# MCU.net
KiCad netlist of a schematic drawn in Altium Designer
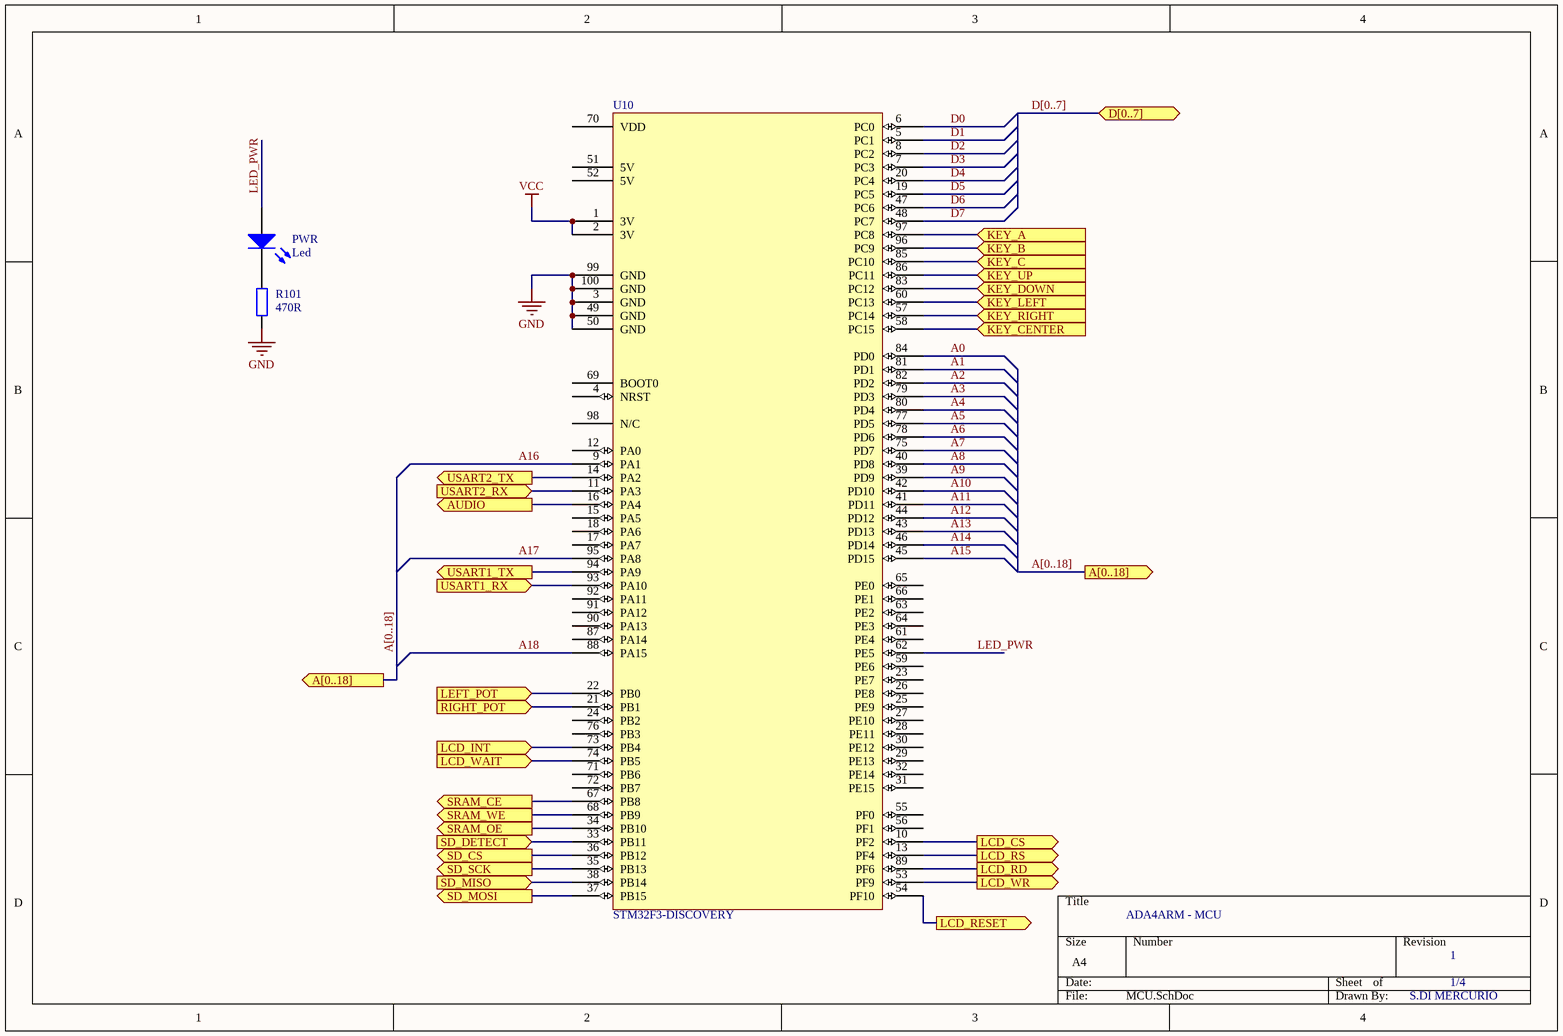
[diagram p0: MCU.SchDoc]

(export (version "E")
  (design (tool "Eeschema 10.0.6"))
  (components
    (comp (ref "PWR") (value "Led") (footprint "OSRAM LO Q971") (libsource (lib "INSA") (part "Led")))
    (comp (ref "R101")
      (value "470R")
      (footprint "RESC3216N")
      (description "Resistor")
      (fields (field (name "Comment") "Res_EU") (field (name "PUBLISHER") "Altium Limited"))
      (libsource (lib "Miscellaneous INSA") (part "Res_EU"))
    )
    (comp (ref "U10")
      (value "STM32F3-DISCOVERY")
      (footprint "STM32F3-DISCOVERY")
      (description "STM32F3-Discovery")
      (libsource (lib "INSA") (part "STM32F3-DISCOVERY"))
    )
  )
  (nets
    (net (code "1") (name "/A0") (class "Default")
      (node (ref "U10") (pin "84") (pinfunction "PD0_84") (pintype "bidirectional"))
    )
    (net (code "2") (name "/A1") (class "Default")
      (node (ref "U10") (pin "81") (pinfunction "PD1_81") (pintype "bidirectional"))
    )
    (net (code "3") (name "/A2") (class "Default")
      (node (ref "U10") (pin "82") (pinfunction "PD2_82") (pintype "bidirectional"))
    )
    (net (code "4") (name "/A3") (class "Default")
      (node (ref "U10") (pin "79") (pinfunction "PD3_79") (pintype "bidirectional"))
    )
    (net (code "5") (name "/A4") (class "Default")
      (node (ref "U10") (pin "80") (pinfunction "PD4_80") (pintype "bidirectional"))
    )
    (net (code "6") (name "/A5") (class "Default")
      (node (ref "U10") (pin "77") (pinfunction "PD5_77") (pintype "bidirectional"))
    )
    (net (code "7") (name "/A6") (class "Default")
      (node (ref "U10") (pin "78") (pinfunction "PD6_78") (pintype "bidirectional"))
    )
    (net (code "8") (name "/A7") (class "Default")
      (node (ref "U10") (pin "75") (pinfunction "PD7_75") (pintype "bidirectional"))
    )
    (net (code "9") (name "/A8") (class "Default")
      (node (ref "U10") (pin "40") (pinfunction "PD8_40") (pintype "bidirectional"))
    )
    (net (code "10") (name "/A9") (class "Default")
      (node (ref "U10") (pin "39") (pinfunction "PD9_39") (pintype "bidirectional"))
    )
    (net (code "11") (name "/A10") (class "Default")
      (node (ref "U10") (pin "42") (pinfunction "PD10_42") (pintype "bidirectional"))
    )
    (net (code "12") (name "/A11") (class "Default")
      (node (ref "U10") (pin "41") (pinfunction "PD11_41") (pintype "bidirectional"))
    )
    (net (code "13") (name "/A12") (class "Default")
      (node (ref "U10") (pin "44") (pinfunction "PD12_44") (pintype "bidirectional"))
    )
    (net (code "14") (name "/A13") (class "Default")
      (node (ref "U10") (pin "43") (pinfunction "PD13_43") (pintype "bidirectional"))
    )
    (net (code "15") (name "/A14") (class "Default")
      (node (ref "U10") (pin "46") (pinfunction "PD14_46") (pintype "bidirectional"))
    )
    (net (code "16") (name "/A15") (class "Default")
      (node (ref "U10") (pin "45") (pinfunction "PD15_45") (pintype "bidirectional"))
    )
    (net (code "17") (name "/A16") (class "Default")
      (node (ref "U10") (pin "9") (pinfunction "PA1_9") (pintype "bidirectional"))
    )
    (net (code "18") (name "/A17") (class "Default")
      (node (ref "U10") (pin "95") (pinfunction "PA8_95") (pintype "bidirectional"))
    )
    (net (code "19") (name "/A18") (class "Default")
      (node (ref "U10") (pin "88") (pinfunction "PA15_88") (pintype "bidirectional"))
    )
    (net (code "20") (name "/AUDIO") (class "Default")
      (node (ref "U10") (pin "16") (pinfunction "PA4_16") (pintype "bidirectional"))
    )
    (net (code "22") (name "/D0") (class "Default")
      (node (ref "U10") (pin "6") (pinfunction "PC0_6") (pintype "bidirectional"))
    )
    (net (code "23") (name "/D1") (class "Default")
      (node (ref "U10") (pin "5") (pinfunction "PC1_5") (pintype "bidirectional"))
    )
    (net (code "24") (name "/D2") (class "Default")
      (node (ref "U10") (pin "8") (pinfunction "PC2_8") (pintype "bidirectional"))
    )
    (net (code "25") (name "/D3") (class "Default")
      (node (ref "U10") (pin "7") (pinfunction "PC3_7") (pintype "bidirectional"))
    )
    (net (code "26") (name "/D4") (class "Default")
      (node (ref "U10") (pin "20") (pinfunction "PC4_20") (pintype "bidirectional"))
    )
    (net (code "27") (name "/D5") (class "Default")
      (node (ref "U10") (pin "19") (pinfunction "PC5_19") (pintype "bidirectional"))
    )
    (net (code "28") (name "/D6") (class "Default")
      (node (ref "U10") (pin "47") (pinfunction "PC6_47") (pintype "bidirectional"))
    )
    (net (code "29") (name "/D7") (class "Default")
      (node (ref "U10") (pin "48") (pinfunction "PC7_48") (pintype "bidirectional"))
    )
    (net (code "31") (name "/KEY_A") (class "Default")
      (node (ref "U10") (pin "97") (pinfunction "PC8_97") (pintype "bidirectional"))
    )
    (net (code "32") (name "/KEY_B") (class "Default")
      (node (ref "U10") (pin "96") (pinfunction "PC9_96") (pintype "bidirectional"))
    )
    (net (code "33") (name "/KEY_C") (class "Default")
      (node (ref "U10") (pin "85") (pinfunction "PC10_85") (pintype "bidirectional"))
    )
    (net (code "34") (name "/KEY_CENTER") (class "Default")
      (node (ref "U10") (pin "58") (pinfunction "PC15_58") (pintype "bidirectional"))
    )
    (net (code "35") (name "/KEY_DOWN") (class "Default")
      (node (ref "U10") (pin "83") (pinfunction "PC12_83") (pintype "bidirectional"))
    )
    (net (code "36") (name "/KEY_LEFT") (class "Default")
      (node (ref "U10") (pin "60") (pinfunction "PC13_60") (pintype "bidirectional"))
    )
    (net (code "37") (name "/KEY_RIGHT") (class "Default")
      (node (ref "U10") (pin "57") (pinfunction "PC14_57") (pintype "bidirectional"))
    )
    (net (code "38") (name "/KEY_UP") (class "Default")
      (node (ref "U10") (pin "86") (pinfunction "PC11_86") (pintype "bidirectional"))
    )
    (net (code "39") (name "/LCD_CS") (class "Default")
      (node (ref "U10") (pin "10") (pinfunction "PF2_10") (pintype "bidirectional"))
    )
    (net (code "40") (name "/LCD_INT") (class "Default")
      (node (ref "U10") (pin "73") (pinfunction "PB4_73") (pintype "bidirectional"))
    )
    (net (code "41") (name "/LCD_RD") (class "Default")
      (node (ref "U10") (pin "89") (pinfunction "PF6_89") (pintype "bidirectional"))
    )
    (net (code "42") (name "/LCD_RESET") (class "Default")
      (node (ref "U10") (pin "54") (pinfunction "PF10_54") (pintype "bidirectional"))
    )
    (net (code "43") (name "/LCD_RS") (class "Default")
      (node (ref "U10") (pin "13") (pinfunction "PF4_13") (pintype "bidirectional"))
    )
    (net (code "44") (name "/LCD_WAIT") (class "Default")
      (node (ref "U10") (pin "74") (pinfunction "PB5_74") (pintype "bidirectional"))
    )
    (net (code "45") (name "/LCD_WR") (class "Default")
      (node (ref "U10") (pin "53") (pinfunction "PF9_53") (pintype "bidirectional"))
    )
    (net (code "46") (name "/LED_PWR") (class "Default")
      (node (ref "PWR") (pin "A") (pinfunction "A_A") (pintype "passive"))
      (node (ref "U10") (pin "62") (pinfunction "PE5_62") (pintype "bidirectional"))
    )
    (net (code "47") (name "/LEFT_POT") (class "Default")
      (node (ref "U10") (pin "22") (pinfunction "PB0_22") (pintype "bidirectional"))
    )
    (net (code "48") (name "/RIGHT_POT") (class "Default")
      (node (ref "U10") (pin "21") (pinfunction "PB1_21") (pintype "bidirectional"))
    )
    (net (code "49") (name "/SD_CS") (class "Default")
      (node (ref "U10") (pin "36") (pinfunction "PB12_36") (pintype "bidirectional"))
    )
    (net (code "50") (name "/SD_DETECT") (class "Default")
      (node (ref "U10") (pin "33") (pinfunction "PB11_33") (pintype "bidirectional"))
    )
    (net (code "51") (name "/SD_MISO") (class "Default")
      (node (ref "U10") (pin "38") (pinfunction "PB14_38") (pintype "bidirectional"))
    )
    (net (code "52") (name "/SD_MOSI") (class "Default")
      (node (ref "U10") (pin "37") (pinfunction "PB15_37") (pintype "bidirectional"))
    )
    (net (code "53") (name "/SD_SCK") (class "Default")
      (node (ref "U10") (pin "35") (pinfunction "PB13_35") (pintype "bidirectional"))
    )
    (net (code "54") (name "/SRAM_CE") (class "Default")
      (node (ref "U10") (pin "67") (pinfunction "PB8_67") (pintype "bidirectional"))
    )
    (net (code "55") (name "/SRAM_OE") (class "Default")
      (node (ref "U10") (pin "34") (pinfunction "PB10_34") (pintype "bidirectional"))
    )
    (net (code "56") (name "/SRAM_WE") (class "Default")
      (node (ref "U10") (pin "68") (pinfunction "PB9_68") (pintype "bidirectional"))
    )
    (net (code "57") (name "/USART1_RX") (class "Default")
      (node (ref "U10") (pin "93") (pinfunction "PA10_93") (pintype "bidirectional"))
    )
    (net (code "58") (name "/USART1_TX") (class "Default")
      (node (ref "U10") (pin "94") (pinfunction "PA9_94") (pintype "bidirectional"))
    )
    (net (code "59") (name "/USART2_RX") (class "Default")
      (node (ref "U10") (pin "11") (pinfunction "PA3_11") (pintype "bidirectional"))
    )
    (net (code "60") (name "/USART2_TX") (class "Default")
      (node (ref "U10") (pin "14") (pinfunction "PA2_14") (pintype "bidirectional"))
    )
    (net (code "61") (name "GND") (class "Default")
      (node (ref "R101") (pin "1") (pinfunction "1_1") (pintype "passive"))
      (node (ref "U10") (pin "100") (pinfunction "GND_100") (pintype "power_in"))
      (node (ref "U10") (pin "3") (pinfunction "GND_3") (pintype "power_in"))
      (node (ref "U10") (pin "49") (pinfunction "GND_49") (pintype "power_in"))
      (node (ref "U10") (pin "50") (pinfunction "GND_50") (pintype "power_in"))
      (node (ref "U10") (pin "99") (pinfunction "GND_99") (pintype "power_in"))
    )
    (net (code "62") (name "Net-(PWR-PadK)") (class "Default")
      (node (ref "PWR") (pin "K") (pinfunction "K_K") (pintype "passive"))
      (node (ref "R101") (pin "2") (pinfunction "2_2") (pintype "passive"))
    )
    (net (code "63") (name "VCC") (class "Default")
      (node (ref "U10") (pin "1") (pinfunction "3V_1") (pintype "power_in"))
      (node (ref "U10") (pin "2") (pinfunction "3V_2") (pintype "power_in"))
    )
    (net (code "64") (name "unconnected-(U10-5V-Pad51)") (class "Default")
      (node (ref "U10") (pin "51") (pinfunction "5V_51") (pintype "power_in"))
    )
    (net (code "65") (name "unconnected-(U10-5V-Pad52)") (class "Default")
      (node (ref "U10") (pin "52") (pinfunction "5V_52") (pintype "power_in"))
    )
    (net (code "66") (name "unconnected-(U10-BOOT0-Pad69)") (class "Default")
      (node (ref "U10") (pin "69") (pinfunction "BOOT0_69") (pintype "passive"))
    )
    (net (code "67") (name "unconnected-(U10-NRST-Pad4)") (class "Default")
      (node (ref "U10") (pin "4") (pinfunction "NRST_4") (pintype "bidirectional"))
    )
    (net (code "68") (name "unconnected-(U10-N{slash}C-Pad98)") (class "Default")
      (node (ref "U10") (pin "98") (pinfunction "N/C_98") (pintype "passive"))
    )
    (net (code "69") (name "unconnected-(U10-PA0-Pad12)") (class "Default")
      (node (ref "U10") (pin "12") (pinfunction "PA0_12") (pintype "bidirectional"))
    )
    (net (code "70") (name "unconnected-(U10-PA5-Pad15)") (class "Default")
      (node (ref "U10") (pin "15") (pinfunction "PA5_15") (pintype "bidirectional"))
    )
    (net (code "71") (name "unconnected-(U10-PA6-Pad18)") (class "Default")
      (node (ref "U10") (pin "18") (pinfunction "PA6_18") (pintype "bidirectional"))
    )
    (net (code "72") (name "unconnected-(U10-PA7-Pad17)") (class "Default")
      (node (ref "U10") (pin "17") (pinfunction "PA7_17") (pintype "bidirectional"))
    )
    (net (code "73") (name "unconnected-(U10-PA11-Pad92)") (class "Default")
      (node (ref "U10") (pin "92") (pinfunction "PA11_92") (pintype "bidirectional"))
    )
    (net (code "74") (name "unconnected-(U10-PA12-Pad91)") (class "Default")
      (node (ref "U10") (pin "91") (pinfunction "PA12_91") (pintype "bidirectional"))
    )
    (net (code "75") (name "unconnected-(U10-PA13-Pad90)") (class "Default")
      (node (ref "U10") (pin "90") (pinfunction "PA13_90") (pintype "bidirectional"))
    )
    (net (code "76") (name "unconnected-(U10-PA14-Pad87)") (class "Default")
      (node (ref "U10") (pin "87") (pinfunction "PA14_87") (pintype "bidirectional"))
    )
    (net (code "77") (name "unconnected-(U10-PB2-Pad24)") (class "Default")
      (node (ref "U10") (pin "24") (pinfunction "PB2_24") (pintype "bidirectional"))
    )
    (net (code "78") (name "unconnected-(U10-PB3-Pad76)") (class "Default")
      (node (ref "U10") (pin "76") (pinfunction "PB3_76") (pintype "bidirectional"))
    )
    (net (code "79") (name "unconnected-(U10-PB6-Pad71)") (class "Default")
      (node (ref "U10") (pin "71") (pinfunction "PB6_71") (pintype "bidirectional"))
    )
    (net (code "80") (name "unconnected-(U10-PB7-Pad72)") (class "Default")
      (node (ref "U10") (pin "72") (pinfunction "PB7_72") (pintype "bidirectional"))
    )
    (net (code "81") (name "unconnected-(U10-PE0-Pad65)") (class "Default")
      (node (ref "U10") (pin "65") (pinfunction "PE0_65") (pintype "bidirectional"))
    )
    (net (code "82") (name "unconnected-(U10-PE1-Pad66)") (class "Default")
      (node (ref "U10") (pin "66") (pinfunction "PE1_66") (pintype "bidirectional"))
    )
    (net (code "83") (name "unconnected-(U10-PE2-Pad63)") (class "Default")
      (node (ref "U10") (pin "63") (pinfunction "PE2_63") (pintype "bidirectional"))
    )
    (net (code "84") (name "unconnected-(U10-PE3-Pad64)") (class "Default")
      (node (ref "U10") (pin "64") (pinfunction "PE3_64") (pintype "bidirectional"))
    )
    (net (code "85") (name "unconnected-(U10-PE4-Pad61)") (class "Default")
      (node (ref "U10") (pin "61") (pinfunction "PE4_61") (pintype "bidirectional"))
    )
    (net (code "86") (name "unconnected-(U10-PE6-Pad59)") (class "Default")
      (node (ref "U10") (pin "59") (pinfunction "PE6_59") (pintype "bidirectional"))
    )
    (net (code "87") (name "unconnected-(U10-PE7-Pad23)") (class "Default")
      (node (ref "U10") (pin "23") (pinfunction "PE7_23") (pintype "bidirectional"))
    )
    (net (code "88") (name "unconnected-(U10-PE8-Pad26)") (class "Default")
      (node (ref "U10") (pin "26") (pinfunction "PE8_26") (pintype "bidirectional"))
    )
    (net (code "89") (name "unconnected-(U10-PE9-Pad25)") (class "Default")
      (node (ref "U10") (pin "25") (pinfunction "PE9_25") (pintype "bidirectional"))
    )
    (net (code "90") (name "unconnected-(U10-PE10-Pad27)") (class "Default")
      (node (ref "U10") (pin "27") (pinfunction "PE10_27") (pintype "bidirectional"))
    )
    (net (code "91") (name "unconnected-(U10-PE11-Pad28)") (class "Default")
      (node (ref "U10") (pin "28") (pinfunction "PE11_28") (pintype "bidirectional"))
    )
    (net (code "92") (name "unconnected-(U10-PE12-Pad30)") (class "Default")
      (node (ref "U10") (pin "30") (pinfunction "PE12_30") (pintype "bidirectional"))
    )
    (net (code "93") (name "unconnected-(U10-PE13-Pad29)") (class "Default")
      (node (ref "U10") (pin "29") (pinfunction "PE13_29") (pintype "bidirectional"))
    )
    (net (code "94") (name "unconnected-(U10-PE14-Pad32)") (class "Default")
      (node (ref "U10") (pin "32") (pinfunction "PE14_32") (pintype "bidirectional"))
    )
    (net (code "95") (name "unconnected-(U10-PE15-Pad31)") (class "Default")
      (node (ref "U10") (pin "31") (pinfunction "PE15_31") (pintype "bidirectional"))
    )
    (net (code "96") (name "unconnected-(U10-PF0-Pad55)") (class "Default")
      (node (ref "U10") (pin "55") (pinfunction "PF0_55") (pintype "bidirectional"))
    )
    (net (code "97") (name "unconnected-(U10-PF1-Pad56)") (class "Default")
      (node (ref "U10") (pin "56") (pinfunction "PF1_56") (pintype "bidirectional"))
    )
    (net (code "98") (name "unconnected-(U10-VDD-Pad70)") (class "Default")
      (node (ref "U10") (pin "70") (pinfunction "VDD_70") (pintype "power_in"))
    )
  )
)
